# SCH_UPS_monitor_2026-08-25.net
KiCad netlist of a schematic drawn in EasyEDA
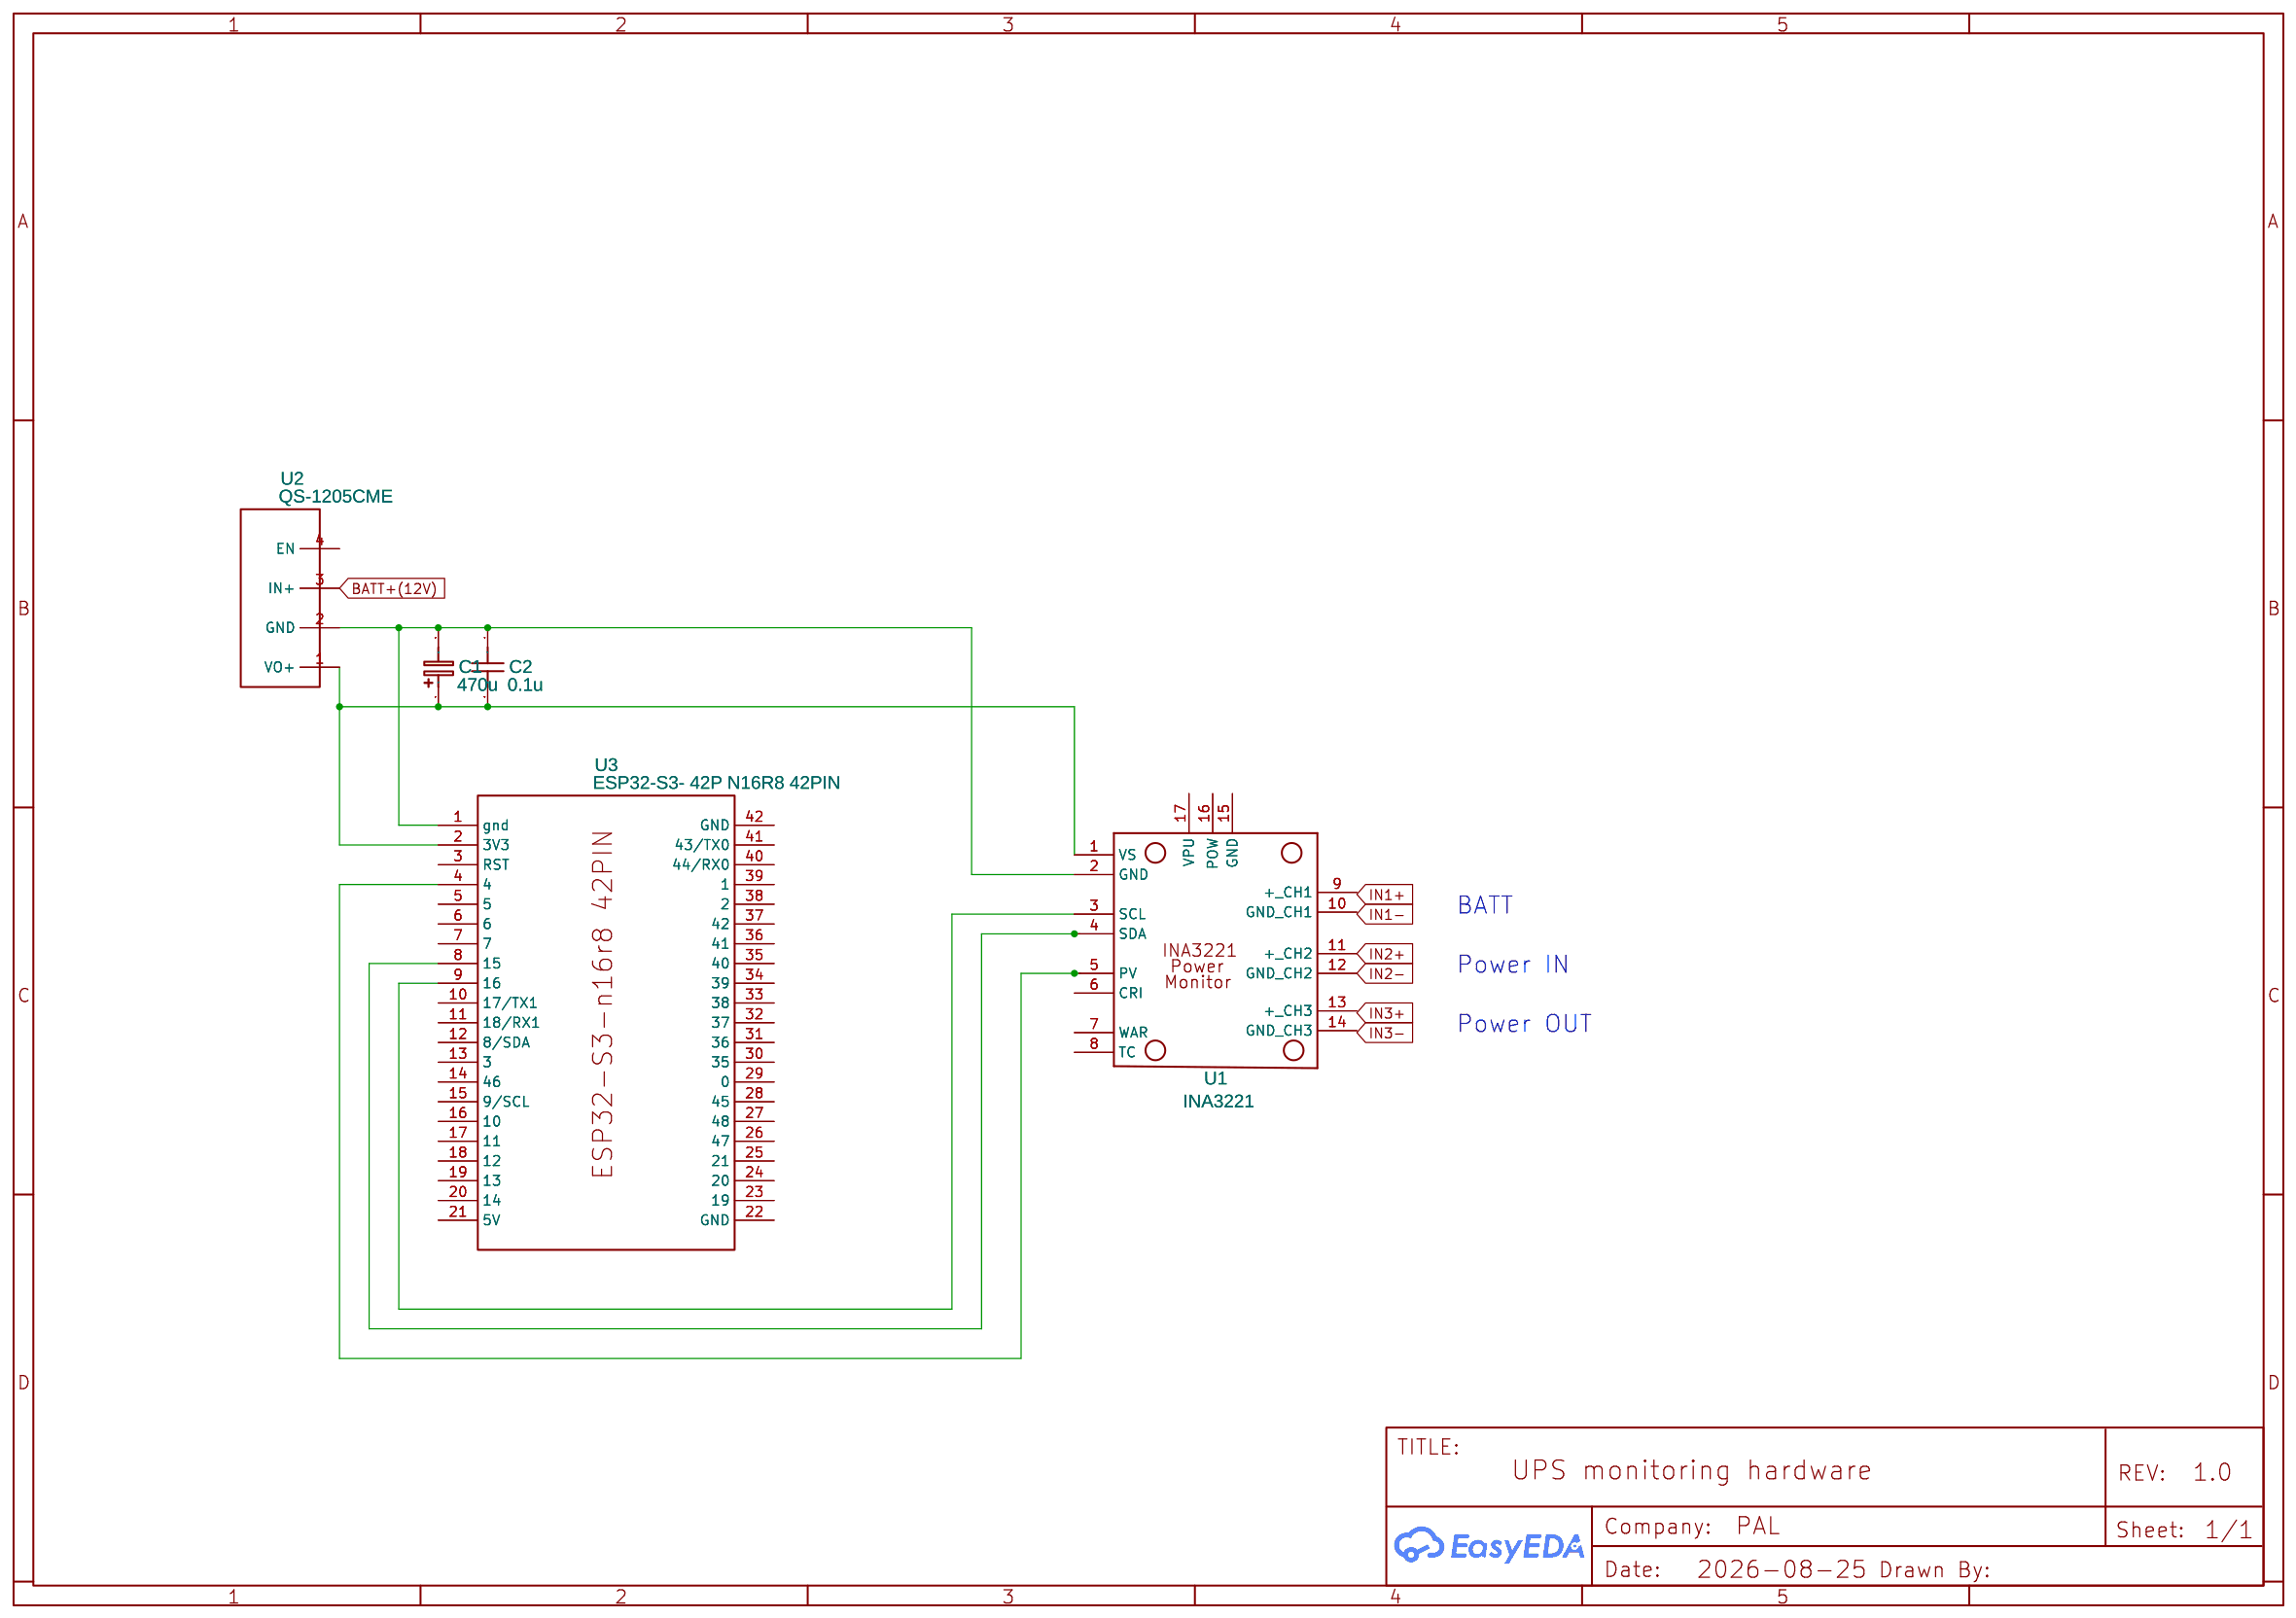
[diagram p0: schematic sheet]

(export (version "E")
  (design (tool "Eeschema 10.0.6"))
  (components
    (comp (ref "C1") (value "470u") (libsource (lib "") (part "C_Tan_SMD_A_EU")))
    (comp (ref "C2") (value "0.1u") (libsource (lib "") (part "C_0603_US")))
    (comp (ref "U1") (value "INA3221") (libsource (lib "") (part "INA3221 ALIEXPRESS NEW MOD")))
    (comp (ref "U2")
      (value "QS-1205CME")
      (fields (field (name "Manufacturer Part") "Mini-DC-DC") (field (name "Manufacturer") "EGBO Store"))
      (libsource (lib "") (part "QS-1205CME"))
    )
    (comp (ref "U3")
      (value "ESP32-S3- 42P N16R8 42PIN")
      (libsource (lib "") (part "ESP32-S3- 42P N16R8 42PIN"))
    )
  )
  (nets
    (net (code "1") (name "BATT+(12V)") (class "Default")
      (node (ref "U2") (pin "3") (pinfunction "IN+_3") (pintype "unspecified"))
    )
    (net (code "4") (name "IN2+") (class "Default")
      (node (ref "U1") (pin "11") (pinfunction "+_CH2_11") (pintype "input"))
    )
    (net (code "5") (name "IN2-") (class "Default")
      (node (ref "U1") (pin "12") (pinfunction "GND_CH2_12") (pintype "input"))
    )
    (net (code "8") (name "Net-(U1-PV)") (class "Default")
      (node (ref "U1") (pin "5") (pinfunction "PV_5") (pintype "input"))
      (node (ref "U3") (pin "4") (pinfunction "4_4") (pintype "unspecified"))
    )
    (net (code "9") (name "Net-(U1-SCL)") (class "Default")
      (node (ref "U1") (pin "3") (pinfunction "SCL_3") (pintype "input"))
      (node (ref "U3") (pin "9") (pinfunction "16_9") (pintype "unspecified"))
    )
    (net (code "10") (name "Net-(U1-SDA)") (class "Default")
      (node (ref "U1") (pin "4") (pinfunction "SDA_4") (pintype "input"))
      (node (ref "U3") (pin "8") (pinfunction "15_8") (pintype "unspecified"))
    )
    (net (code "11") (name "Net-(U1-VS)") (class "Default")
      (node (ref "C1") (pin "1") (pinfunction "1_1") (pintype "unspecified"))
      (node (ref "C2") (pin "2") (pinfunction "2_2") (pintype "unspecified"))
      (node (ref "U1") (pin "1") (pinfunction "VS_1") (pintype "input"))
      (node (ref "U2") (pin "1") (pinfunction "VO+_1") (pintype "unspecified"))
      (node (ref "U3") (pin "2") (pinfunction "3V3_2") (pintype "unspecified"))
    )
    (net (code "12") (name "Net-(U2-GND)") (class "Default")
      (node (ref "C1") (pin "2") (pinfunction "2_2") (pintype "unspecified"))
      (node (ref "C2") (pin "1") (pinfunction "1_1") (pintype "unspecified"))
      (node (ref "U1") (pin "2") (pinfunction "GND_2") (pintype "input"))
      (node (ref "U2") (pin "2") (pinfunction "GND_2") (pintype "unspecified"))
      (node (ref "U3") (pin "1") (pinfunction "gnd_1") (pintype "unspecified"))
    )
    (net (code "13") (name "unconnected-(U1-+_CH1-Pad9)") (class "Default")
      (node (ref "U1") (pin "9") (pinfunction "+_CH1_9") (pintype "passive"))
    )
    (net (code "14") (name "unconnected-(U1-+_CH3-Pad13)") (class "Default")
      (node (ref "U1") (pin "13") (pinfunction "+_CH3_13") (pintype "passive"))
    )
    (net (code "15") (name "unconnected-(U1-CRI-Pad6)") (class "Default")
      (node (ref "U1") (pin "6") (pinfunction "CRI_6") (pintype "passive"))
    )
    (net (code "16") (name "unconnected-(U1-GND-Pad15)") (class "Default")
      (node (ref "U1") (pin "15") (pinfunction "GND_15") (pintype "passive"))
    )
    (net (code "17") (name "unconnected-(U1-GND_CH1-Pad10)") (class "Default")
      (node (ref "U1") (pin "10") (pinfunction "GND_CH1_10") (pintype "unspecified"))
    )
    (net (code "18") (name "unconnected-(U1-GND_CH3-Pad14)") (class "Default")
      (node (ref "U1") (pin "14") (pinfunction "GND_CH3_14") (pintype "input"))
    )
    (net (code "19") (name "unconnected-(U1-POW-Pad16)") (class "Default")
      (node (ref "U1") (pin "16") (pinfunction "POW_16") (pintype "input"))
    )
    (net (code "20") (name "unconnected-(U1-TC-Pad8)") (class "Default")
      (node (ref "U1") (pin "8") (pinfunction "TC_8") (pintype "input"))
    )
    (net (code "21") (name "unconnected-(U1-VPU-Pad17)") (class "Default")
      (node (ref "U1") (pin "17") (pinfunction "VPU_17") (pintype "unspecified"))
    )
    (net (code "22") (name "unconnected-(U1-WAR-Pad7)") (class "Default")
      (node (ref "U1") (pin "7") (pinfunction "WAR_7") (pintype "input"))
    )
    (net (code "23") (name "unconnected-(U2-EN-Pad4)") (class "Default")
      (node (ref "U2") (pin "4") (pinfunction "EN_4") (pintype "unspecified"))
    )
    (net (code "24") (name "unconnected-(U3-0-Pad29)") (class "Default")
      (node (ref "U3") (pin "29") (pinfunction "0_29") (pintype "unspecified"))
    )
    (net (code "25") (name "unconnected-(U3-1-Pad39)") (class "Default")
      (node (ref "U3") (pin "39") (pinfunction "1_39") (pintype "unspecified"))
    )
    (net (code "26") (name "unconnected-(U3-2-Pad38)") (class "Default")
      (node (ref "U3") (pin "38") (pinfunction "2_38") (pintype "unspecified"))
    )
    (net (code "27") (name "unconnected-(U3-3-Pad13)") (class "Default")
      (node (ref "U3") (pin "13") (pinfunction "3_13") (pintype "unspecified"))
    )
    (net (code "28") (name "unconnected-(U3-5V-Pad21)") (class "Default")
      (node (ref "U3") (pin "21") (pinfunction "5V_21") (pintype "unspecified"))
    )
    (net (code "29") (name "unconnected-(U3-8{slash}SDA-Pad12)") (class "Default")
      (node (ref "U3") (pin "12") (pinfunction "8/SDA_12") (pintype "unspecified"))
    )
    (net (code "30") (name "unconnected-(U3-9{slash}SCL-Pad15)") (class "Default")
      (node (ref "U3") (pin "15") (pinfunction "9/SCL_15") (pintype "unspecified"))
    )
    (net (code "31") (name "unconnected-(U3-10-Pad16)") (class "Default")
      (node (ref "U3") (pin "16") (pinfunction "10_16") (pintype "unspecified"))
    )
    (net (code "32") (name "unconnected-(U3-11-Pad17)") (class "Default")
      (node (ref "U3") (pin "17") (pinfunction "11_17") (pintype "unspecified"))
    )
    (net (code "33") (name "unconnected-(U3-12-Pad18)") (class "Default")
      (node (ref "U3") (pin "18") (pinfunction "12_18") (pintype "unspecified"))
    )
    (net (code "34") (name "unconnected-(U3-13-Pad19)") (class "Default")
      (node (ref "U3") (pin "19") (pinfunction "13_19") (pintype "unspecified"))
    )
    (net (code "35") (name "unconnected-(U3-14-Pad20)") (class "Default")
      (node (ref "U3") (pin "20") (pinfunction "14_20") (pintype "unspecified"))
    )
    (net (code "36") (name "unconnected-(U3-17{slash}TX1-Pad10)") (class "Default")
      (node (ref "U3") (pin "10") (pinfunction "17/TX1_10") (pintype "unspecified"))
    )
    (net (code "37") (name "unconnected-(U3-18{slash}RX1-Pad11)") (class "Default")
      (node (ref "U3") (pin "11") (pinfunction "18/RX1_11") (pintype "unspecified"))
    )
    (net (code "38") (name "unconnected-(U3-19-Pad23)") (class "Default")
      (node (ref "U3") (pin "23") (pinfunction "19_23") (pintype "unspecified"))
    )
    (net (code "39") (name "unconnected-(U3-20-Pad24)") (class "Default")
      (node (ref "U3") (pin "24") (pinfunction "20_24") (pintype "unspecified"))
    )
    (net (code "40") (name "unconnected-(U3-21-Pad25)") (class "Default")
      (node (ref "U3") (pin "25") (pinfunction "21_25") (pintype "unspecified"))
    )
    (net (code "41") (name "unconnected-(U3-35-Pad30)") (class "Default")
      (node (ref "U3") (pin "30") (pinfunction "35_30") (pintype "unspecified"))
    )
    (net (code "42") (name "unconnected-(U3-36-Pad31)") (class "Default")
      (node (ref "U3") (pin "31") (pinfunction "36_31") (pintype "unspecified"))
    )
    (net (code "43") (name "unconnected-(U3-37-Pad32)") (class "Default")
      (node (ref "U3") (pin "32") (pinfunction "37_32") (pintype "unspecified"))
    )
    (net (code "44") (name "unconnected-(U3-38-Pad33)") (class "Default")
      (node (ref "U3") (pin "33") (pinfunction "38_33") (pintype "unspecified"))
    )
    (net (code "45") (name "unconnected-(U3-39-Pad34)") (class "Default")
      (node (ref "U3") (pin "34") (pinfunction "39_34") (pintype "unspecified"))
    )
    (net (code "46") (name "unconnected-(U3-40-Pad35)") (class "Default")
      (node (ref "U3") (pin "35") (pinfunction "40_35") (pintype "unspecified"))
    )
    (net (code "47") (name "unconnected-(U3-41-Pad36)") (class "Default")
      (node (ref "U3") (pin "36") (pinfunction "41_36") (pintype "unspecified"))
    )
    (net (code "48") (name "unconnected-(U3-42-Pad37)") (class "Default")
      (node (ref "U3") (pin "37") (pinfunction "42_37") (pintype "unspecified"))
    )
    (net (code "49") (name "unconnected-(U3-43{slash}TX0-Pad41)") (class "Default")
      (node (ref "U3") (pin "41") (pinfunction "43/TX0_41") (pintype "unspecified"))
    )
    (net (code "50") (name "unconnected-(U3-44{slash}RX0-Pad40)") (class "Default")
      (node (ref "U3") (pin "40") (pinfunction "44/RX0_40") (pintype "unspecified"))
    )
    (net (code "51") (name "unconnected-(U3-45-Pad28)") (class "Default")
      (node (ref "U3") (pin "28") (pinfunction "45_28") (pintype "unspecified"))
    )
    (net (code "52") (name "unconnected-(U3-46-Pad14)") (class "Default")
      (node (ref "U3") (pin "14") (pinfunction "46_14") (pintype "unspecified"))
    )
    (net (code "53") (name "unconnected-(U3-47-Pad26)") (class "Default")
      (node (ref "U3") (pin "26") (pinfunction "47_26") (pintype "unspecified"))
    )
    (net (code "54") (name "unconnected-(U3-48-Pad27)") (class "Default")
      (node (ref "U3") (pin "27") (pinfunction "48_27") (pintype "unspecified"))
    )
    (net (code "55") (name "unconnected-(U3-GND-Pad22)") (class "Default")
      (node (ref "U3") (pin "22") (pinfunction "GND_22") (pintype "unspecified"))
    )
    (net (code "56") (name "unconnected-(U3-GND-Pad42)") (class "Default")
      (node (ref "U3") (pin "42") (pinfunction "GND_42") (pintype "unspecified"))
    )
    (net (code "57") (name "unconnected-(U3-Pad5)") (class "Default")
      (node (ref "U3") (pin "5") (pinfunction "5_5") (pintype "unspecified"))
    )
    (net (code "58") (name "unconnected-(U3-Pad6)") (class "Default")
      (node (ref "U3") (pin "6") (pinfunction "6_6") (pintype "unspecified"))
    )
    (net (code "59") (name "unconnected-(U3-Pad7)") (class "Default")
      (node (ref "U3") (pin "7") (pinfunction "7_7") (pintype "unspecified"))
    )
    (net (code "60") (name "unconnected-(U3-RST-Pad3)") (class "Default")
      (node (ref "U3") (pin "3") (pinfunction "RST_3") (pintype "unspecified"))
    )
  )
)
